# das_uhr.net
KiCad netlist of a schematic drawn in EAGLE
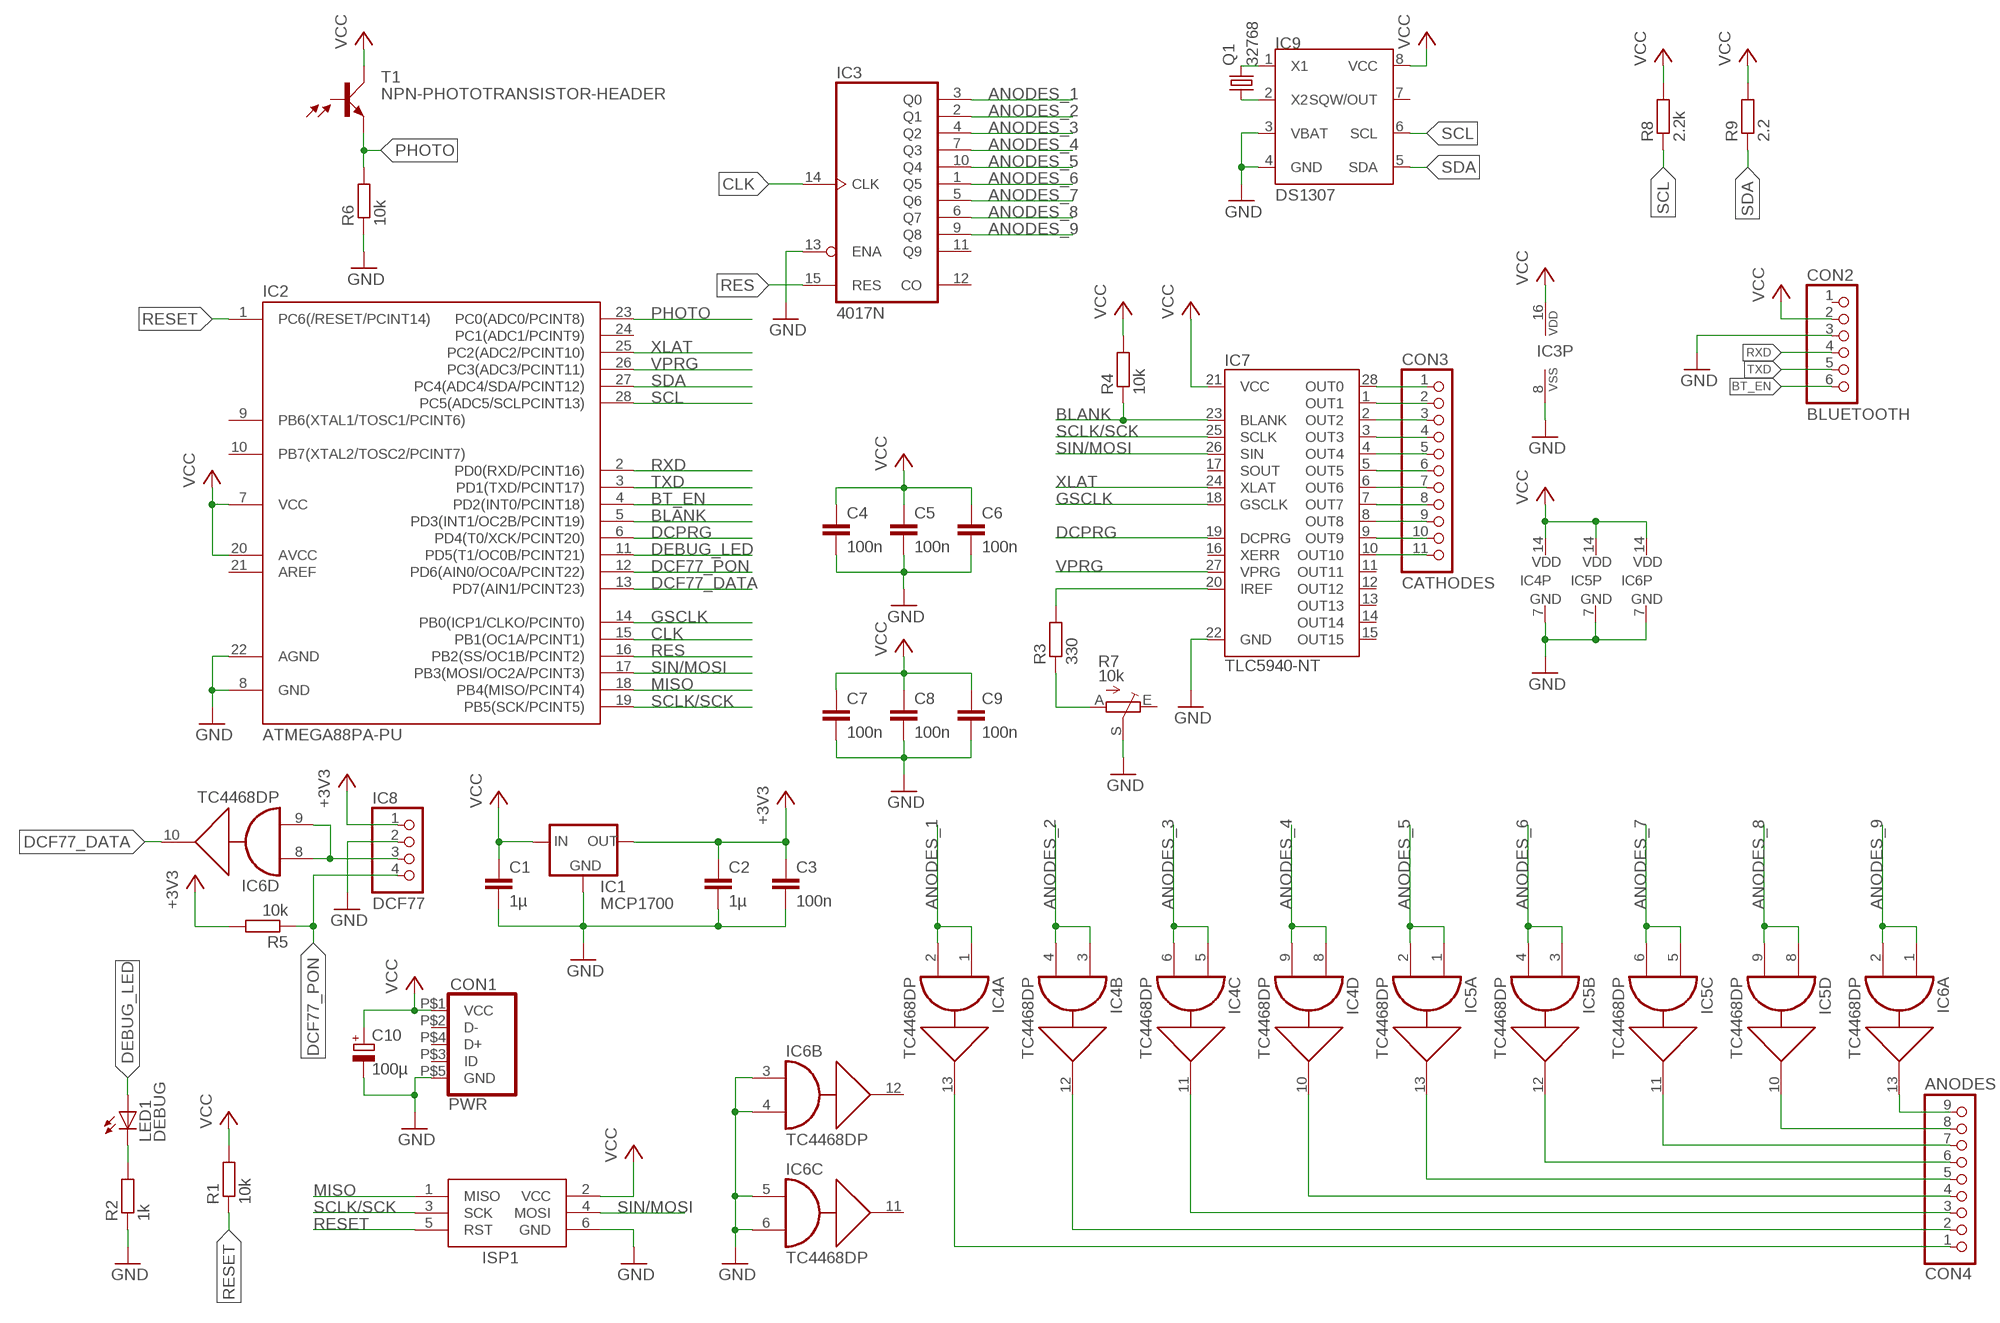
[diagram p0: schematic, sheet 1]

(export (version "E")
  (design (tool "Eeschema 10.0.6"))
  (components
    (comp (ref "C1")
      (value "1µ")
      (footprint "eagle-import:C050-024X044")
      (libsource (lib "eagle-import") (part "C050-024X044"))
    )
    (comp (ref "C2")
      (value "1µ")
      (footprint "eagle-import:C050-024X044")
      (libsource (lib "eagle-import") (part "C050-024X044"))
    )
    (comp (ref "C3")
      (value "100n")
      (footprint "eagle-import:C050-024X044")
      (libsource (lib "eagle-import") (part "C050-024X044"))
    )
    (comp (ref "C4")
      (value "100n")
      (footprint "eagle-import:C050-024X044")
      (libsource (lib "eagle-import") (part "C050-024X044"))
    )
    (comp (ref "C5")
      (value "100n")
      (footprint "eagle-import:C050-024X044")
      (libsource (lib "eagle-import") (part "C050-024X044"))
    )
    (comp (ref "C6")
      (value "100n")
      (footprint "eagle-import:C050-024X044")
      (libsource (lib "eagle-import") (part "C050-024X044"))
    )
    (comp (ref "C7")
      (value "100n")
      (footprint "eagle-import:C050-024X044")
      (libsource (lib "eagle-import") (part "C050-024X044"))
    )
    (comp (ref "C8")
      (value "100n")
      (footprint "eagle-import:C050-024X044")
      (libsource (lib "eagle-import") (part "C050-024X044"))
    )
    (comp (ref "C9")
      (value "100n")
      (footprint "eagle-import:C050-024X044")
      (libsource (lib "eagle-import") (part "C050-024X044"))
    )
    (comp (ref "C10")
      (value "100µ")
      (footprint "eagle-import:E2,5-5")
      (libsource (lib "eagle-import") (part "CPOL-EUE2.5-5"))
    )
    (comp (ref "CON1")
      (value "PWR")
      (footprint "eagle-import:HIROSE-ZX62-AB-5PA(11)")
      (libsource (lib "eagle-import") (part "USB-RECEPTABLE-HIROSE-ZX62-AB-5PA(11)"))
    )
    (comp (ref "CON2")
      (value "BLUETOOTH")
      (footprint "eagle-import:1X06")
      (libsource (lib "eagle-import") (part "PINHD-1X6"))
    )
    (comp (ref "CON3")
      (value "CATHODES")
      (footprint "eagle-import:1X11")
      (libsource (lib "eagle-import") (part "PINHD-1X11"))
    )
    (comp (ref "CON4")
      (value "ANODES")
      (footprint "eagle-import:1X09")
      (libsource (lib "eagle-import") (part "PINHD-1X9"))
    )
    (comp (ref "IC1")
      (value "MCP1700")
      (footprint "eagle-import:TO92-INLINE")
      (libsource (lib "eagle-import") (part "MCP1700INLINE"))
    )
    (comp (ref "IC2")
      (value "ATMEGA88PA-PU")
      (footprint "eagle-import:DIL28-3")
      (libsource (lib "eagle-import") (part "MEGA48/88/168-PU"))
    )
    (comp (ref "IC3")
      (value "4017N")
      (footprint "eagle-import:DIL16")
      (libsource (lib "eagle-import") (part "4017N"))
    )
    (comp (ref "IC4")
      (value "TC4468DP")
      (footprint "eagle-import:DIL14")
      (fields (field (name "MF") "MICROCHIP") (field (name "MPN") "TC4468CPD"))
      (libsource (lib "eagle-import") (part "TC4468DP"))
    )
    (comp (ref "IC5")
      (value "TC4468DP")
      (footprint "eagle-import:DIL14")
      (fields (field (name "MF") "MICROCHIP") (field (name "MPN") "TC4468CPD"))
      (libsource (lib "eagle-import") (part "TC4468DP"))
    )
    (comp (ref "IC6")
      (value "TC4468DP")
      (footprint "eagle-import:DIL14")
      (fields (field (name "MF") "MICROCHIP") (field (name "MPN") "TC4468CPD"))
      (libsource (lib "eagle-import") (part "TC4468DP"))
    )
    (comp (ref "IC7")
      (value "TLC5940-NT")
      (footprint "eagle-import:DIL28-3")
      (libsource (lib "eagle-import") (part "TLC5940-NT"))
    )
    (comp (ref "IC8")
      (value "DCF77")
      (footprint "eagle-import:1X04")
      (libsource (lib "eagle-import") (part "PINHD-1X4"))
    )
    (comp (ref "IC9")
      (value "DS1307")
      (footprint "eagle-import:DIL08")
      (libsource (lib "eagle-import") (part "DS1307"))
    )
    (comp (ref "ISP1")
      (value "AVRISP-6")
      (footprint "eagle-import:AVRISP")
      (libsource (lib "eagle-import") (part "AVRISP-6"))
    )
    (comp (ref "LED1")
      (value "DEBUG")
      (footprint "eagle-import:LED3MM")
      (libsource (lib "eagle-import") (part "LED3MM"))
    )
    (comp (ref "Q1")
      (value "32768")
      (footprint "eagle-import:TC26V")
      (libsource (lib "eagle-import") (part "CRYSTALTC26V"))
    )
    (comp (ref "R1")
      (value "10k")
      (footprint "eagle-import:0207_7")
      (libsource (lib "eagle-import") (part "R-EU_0207/7"))
    )
    (comp (ref "R2")
      (value "1k")
      (footprint "eagle-import:0207_7")
      (libsource (lib "eagle-import") (part "R-EU_0207/7"))
    )
    (comp (ref "R3")
      (value "330")
      (footprint "eagle-import:0207_7")
      (libsource (lib "eagle-import") (part "R-EU_0207/7"))
    )
    (comp (ref "R4")
      (value "10k")
      (footprint "eagle-import:0207_7")
      (libsource (lib "eagle-import") (part "R-EU_0207/7"))
    )
    (comp (ref "R5")
      (value "10k")
      (footprint "eagle-import:0207_7")
      (libsource (lib "eagle-import") (part "R-EU_0207/7"))
    )
    (comp (ref "R6")
      (value "10k")
      (footprint "eagle-import:0207_7")
      (libsource (lib "eagle-import") (part "R-EU_0207/7"))
    )
    (comp (ref "R7")
      (value "10k")
      (footprint "eagle-import:S63P")
      (libsource (lib "eagle-import") (part "TRIM_EU-S63P"))
    )
    (comp (ref "R8")
      (value "2.2k")
      (footprint "eagle-import:0207_7")
      (libsource (lib "eagle-import") (part "R-EU_0207/7"))
    )
    (comp (ref "R9")
      (value "2.2")
      (footprint "eagle-import:0207_7")
      (libsource (lib "eagle-import") (part "R-EU_0207/7"))
    )
    (comp (ref "T1")
      (value "NPN-PHOTOTRANSISTOR-HEADER")
      (footprint "eagle-import:1X02-S")
      (libsource (lib "eagle-import") (part "NPN-PHOTOTRANSISTOR-HEADER"))
    )
  )
  (nets
    (net (code "1") (name "+3V3") (class "Default")
      (node (ref "C2") (pin "1") (pinfunction "1_1") (pintype "passive"))
      (node (ref "C3") (pin "1") (pinfunction "1_1") (pintype "passive"))
      (node (ref "IC1") (pin "3") (pinfunction "OUT_3") (pintype "passive"))
      (node (ref "IC8") (pin "1") (pinfunction "1_1") (pintype "passive"))
      (node (ref "R5") (pin "2") (pinfunction "2_2") (pintype "passive"))
    )
    (net (code "2") (name "/ANODES_1") (class "Default")
      (node (ref "IC3") (pin "3") (pinfunction "Q0_3") (pintype "output"))
      (node (ref "IC4") (pin "1") (pinfunction "A_1") (pintype "input"))
      (node (ref "IC4") (pin "2") (pinfunction "B_2") (pintype "input"))
    )
    (net (code "3") (name "/ANODES_2") (class "Default")
      (node (ref "IC3") (pin "2") (pinfunction "Q1_2") (pintype "output"))
      (node (ref "IC4") (pin "3") (pinfunction "A_3") (pintype "input"))
      (node (ref "IC4") (pin "4") (pinfunction "B_4") (pintype "input"))
    )
    (net (code "4") (name "/ANODES_3") (class "Default")
      (node (ref "IC3") (pin "4") (pinfunction "Q2_4") (pintype "output"))
      (node (ref "IC4") (pin "5") (pinfunction "A_5") (pintype "input"))
      (node (ref "IC4") (pin "6") (pinfunction "B_6") (pintype "input"))
    )
    (net (code "5") (name "/ANODES_4") (class "Default")
      (node (ref "IC3") (pin "7") (pinfunction "Q3_7") (pintype "output"))
      (node (ref "IC4") (pin "8") (pinfunction "A_8") (pintype "input"))
      (node (ref "IC4") (pin "9") (pinfunction "B_9") (pintype "input"))
    )
    (net (code "6") (name "/ANODES_5") (class "Default")
      (node (ref "IC3") (pin "10") (pinfunction "Q4_10") (pintype "output"))
      (node (ref "IC5") (pin "1") (pinfunction "A_1") (pintype "input"))
      (node (ref "IC5") (pin "2") (pinfunction "B_2") (pintype "input"))
    )
    (net (code "7") (name "/ANODES_6") (class "Default")
      (node (ref "IC3") (pin "1") (pinfunction "Q5_1") (pintype "output"))
      (node (ref "IC5") (pin "3") (pinfunction "A_3") (pintype "input"))
      (node (ref "IC5") (pin "4") (pinfunction "B_4") (pintype "input"))
    )
    (net (code "8") (name "/ANODES_7") (class "Default")
      (node (ref "IC3") (pin "5") (pinfunction "Q6_5") (pintype "output"))
      (node (ref "IC5") (pin "5") (pinfunction "A_5") (pintype "input"))
      (node (ref "IC5") (pin "6") (pinfunction "B_6") (pintype "input"))
    )
    (net (code "9") (name "/ANODES_8") (class "Default")
      (node (ref "IC3") (pin "6") (pinfunction "Q7_6") (pintype "output"))
      (node (ref "IC5") (pin "8") (pinfunction "A_8") (pintype "input"))
      (node (ref "IC5") (pin "9") (pinfunction "B_9") (pintype "input"))
    )
    (net (code "10") (name "/ANODES_9") (class "Default")
      (node (ref "IC3") (pin "9") (pinfunction "Q8_9") (pintype "output"))
      (node (ref "IC6") (pin "1") (pinfunction "A_1") (pintype "input"))
      (node (ref "IC6") (pin "2") (pinfunction "B_2") (pintype "input"))
    )
    (net (code "11") (name "/BLANK") (class "Default")
      (node (ref "IC2") (pin "5") (pinfunction "PD3(INT1/OC2B/PCINT19)_5") (pintype "bidirectional"))
      (node (ref "IC7") (pin "23") (pinfunction "BLANK_23") (pintype "bidirectional"))
      (node (ref "R4") (pin "1") (pinfunction "1_1") (pintype "passive"))
    )
    (net (code "12") (name "/DCPRG") (class "Default")
      (node (ref "IC2") (pin "6") (pinfunction "PD4(T0/XCK/PCINT20)_6") (pintype "bidirectional"))
      (node (ref "IC7") (pin "19") (pinfunction "DCPRG_19") (pintype "bidirectional"))
    )
    (net (code "13") (name "/GSCLK") (class "Default")
      (node (ref "IC2") (pin "14") (pinfunction "PB0(ICP1/CLKO/PCINT0)_14") (pintype "bidirectional"))
      (node (ref "IC7") (pin "18") (pinfunction "GSCLK_18") (pintype "bidirectional"))
    )
    (net (code "14") (name "/MISO") (class "Default")
      (node (ref "IC2") (pin "18") (pinfunction "PB4(MISO/PCINT4)_18") (pintype "bidirectional"))
      (node (ref "ISP1") (pin "1") (pinfunction "MISO_1") (pintype "input"))
    )
    (net (code "15") (name "/SCLK{slash}SCK") (class "Default")
      (node (ref "IC2") (pin "19") (pinfunction "PB5(SCK/PCINT5)_19") (pintype "bidirectional"))
      (node (ref "IC7") (pin "25") (pinfunction "SCLK_25") (pintype "bidirectional"))
      (node (ref "ISP1") (pin "3") (pinfunction "SCK_3") (pintype "output"))
    )
    (net (code "16") (name "/SIN{slash}MOSI") (class "Default")
      (node (ref "IC2") (pin "17") (pinfunction "PB3(MOSI/OC2A/PCINT3)_17") (pintype "bidirectional"))
      (node (ref "IC7") (pin "26") (pinfunction "SIN_26") (pintype "bidirectional"))
      (node (ref "ISP1") (pin "4") (pinfunction "MOSI_4") (pintype "output"))
    )
    (net (code "17") (name "/VPRG") (class "Default")
      (node (ref "IC2") (pin "26") (pinfunction "PC3(ADC3/PCINT11)_26") (pintype "bidirectional"))
      (node (ref "IC7") (pin "27") (pinfunction "VPRG_27") (pintype "bidirectional"))
    )
    (net (code "18") (name "/XLAT") (class "Default")
      (node (ref "IC2") (pin "25") (pinfunction "PC2(ADC2/PCINT10)_25") (pintype "bidirectional"))
      (node (ref "IC7") (pin "24") (pinfunction "XLAT_24") (pintype "bidirectional"))
    )
    (net (code "19") (name "BT_EN") (class "Default")
      (node (ref "CON2") (pin "6") (pinfunction "6_6") (pintype "passive"))
      (node (ref "IC2") (pin "4") (pinfunction "PD2(INT0/PCINT18)_4") (pintype "bidirectional"))
    )
    (net (code "20") (name "CLK") (class "Default")
      (node (ref "IC2") (pin "15") (pinfunction "PB1(OC1A/PCINT1)_15") (pintype "bidirectional"))
      (node (ref "IC3") (pin "14") (pinfunction "CLK_14") (pintype "input"))
    )
    (net (code "21") (name "DCF77_DATA") (class "Default")
      (node (ref "IC2") (pin "13") (pinfunction "PD7(AIN1/PCINT23)_13") (pintype "bidirectional"))
      (node (ref "IC6") (pin "10") (pinfunction "Y_10") (pintype "output"))
    )
    (net (code "22") (name "DCF77_PON") (class "Default")
      (node (ref "IC2") (pin "12") (pinfunction "PD6(AIN0/OC0A/PCINT22)_12") (pintype "bidirectional"))
      (node (ref "IC8") (pin "4") (pinfunction "4_4") (pintype "passive"))
      (node (ref "R5") (pin "1") (pinfunction "1_1") (pintype "passive"))
    )
    (net (code "23") (name "DEBUG_LED") (class "Default")
      (node (ref "IC2") (pin "11") (pinfunction "PD5(T1/OC0B/PCINT21)_11") (pintype "bidirectional"))
      (node (ref "LED1") (pin "A") (pinfunction "A_A") (pintype "passive"))
    )
    (net (code "24") (name "GND") (class "Default")
      (node (ref "C1") (pin "2") (pinfunction "2_2") (pintype "passive"))
      (node (ref "C10") (pin "-") (pinfunction "-_-") (pintype "passive"))
      (node (ref "C2") (pin "2") (pinfunction "2_2") (pintype "passive"))
      (node (ref "C3") (pin "2") (pinfunction "2_2") (pintype "passive"))
      (node (ref "C4") (pin "2") (pinfunction "2_2") (pintype "passive"))
      (node (ref "C5") (pin "2") (pinfunction "2_2") (pintype "passive"))
      (node (ref "C6") (pin "2") (pinfunction "2_2") (pintype "passive"))
      (node (ref "C7") (pin "2") (pinfunction "2_2") (pintype "passive"))
      (node (ref "C8") (pin "2") (pinfunction "2_2") (pintype "passive"))
      (node (ref "C9") (pin "2") (pinfunction "2_2") (pintype "passive"))
      (node (ref "CON1") (pin "P$5") (pinfunction "GND_P$5") (pintype "bidirectional"))
      (node (ref "CON2") (pin "3") (pinfunction "3_3") (pintype "passive"))
      (node (ref "IC1") (pin "1") (pinfunction "GND_1") (pintype "input"))
      (node (ref "IC2") (pin "22") (pinfunction "AGND_22") (pintype "power_in"))
      (node (ref "IC2") (pin "8") (pinfunction "GND_8") (pintype "power_in"))
      (node (ref "IC3") (pin "13") (pinfunction "ENA_13") (pintype "input"))
      (node (ref "IC3") (pin "8") (pinfunction "VSS_8") (pintype "power_in"))
      (node (ref "IC4") (pin "7") (pinfunction "GND_7") (pintype "power_in"))
      (node (ref "IC5") (pin "7") (pinfunction "GND_7") (pintype "power_in"))
      (node (ref "IC6") (pin "3") (pinfunction "A_3") (pintype "input"))
      (node (ref "IC6") (pin "4") (pinfunction "B_4") (pintype "input"))
      (node (ref "IC6") (pin "5") (pinfunction "A_5") (pintype "input"))
      (node (ref "IC6") (pin "6") (pinfunction "B_6") (pintype "input"))
      (node (ref "IC6") (pin "7") (pinfunction "GND_7") (pintype "power_in"))
      (node (ref "IC7") (pin "22") (pinfunction "GND_22") (pintype "bidirectional"))
      (node (ref "IC8") (pin "2") (pinfunction "2_2") (pintype "passive"))
      (node (ref "IC9") (pin "3") (pinfunction "VBAT_3") (pintype "power_in"))
      (node (ref "IC9") (pin "4") (pinfunction "GND_4") (pintype "power_in"))
      (node (ref "ISP1") (pin "6") (pinfunction "GND_6") (pintype "power_in"))
      (node (ref "R2") (pin "1") (pinfunction "1_1") (pintype "passive"))
      (node (ref "R6") (pin "1") (pinfunction "1_1") (pintype "passive"))
      (node (ref "R7") (pin "S") (pinfunction "S_S") (pintype "passive"))
    )
    (net (code "25") (name "Net-(IC4A-Y)") (class "Default")
      (node (ref "CON4") (pin "1") (pinfunction "1_1") (pintype "passive"))
      (node (ref "IC4") (pin "13") (pinfunction "Y_13") (pintype "output"))
    )
    (net (code "26") (name "Net-(IC4B-Y)") (class "Default")
      (node (ref "CON4") (pin "2") (pinfunction "2_2") (pintype "passive"))
      (node (ref "IC4") (pin "12") (pinfunction "Y_12") (pintype "output"))
    )
    (net (code "27") (name "Net-(IC4C-Y)") (class "Default")
      (node (ref "CON4") (pin "3") (pinfunction "3_3") (pintype "passive"))
      (node (ref "IC4") (pin "11") (pinfunction "Y_11") (pintype "output"))
    )
    (net (code "28") (name "Net-(IC4D-Y)") (class "Default")
      (node (ref "CON4") (pin "4") (pinfunction "4_4") (pintype "passive"))
      (node (ref "IC4") (pin "10") (pinfunction "Y_10") (pintype "output"))
    )
    (net (code "29") (name "Net-(IC5A-Y)") (class "Default")
      (node (ref "CON4") (pin "5") (pinfunction "5_5") (pintype "passive"))
      (node (ref "IC5") (pin "13") (pinfunction "Y_13") (pintype "output"))
    )
    (net (code "30") (name "Net-(IC5B-Y)") (class "Default")
      (node (ref "CON4") (pin "6") (pinfunction "6_6") (pintype "passive"))
      (node (ref "IC5") (pin "12") (pinfunction "Y_12") (pintype "output"))
    )
    (net (code "31") (name "Net-(IC5C-Y)") (class "Default")
      (node (ref "CON4") (pin "7") (pinfunction "7_7") (pintype "passive"))
      (node (ref "IC5") (pin "11") (pinfunction "Y_11") (pintype "output"))
    )
    (net (code "32") (name "Net-(IC5D-Y)") (class "Default")
      (node (ref "CON4") (pin "8") (pinfunction "8_8") (pintype "passive"))
      (node (ref "IC5") (pin "10") (pinfunction "Y_10") (pintype "output"))
    )
    (net (code "33") (name "Net-(IC6A-Y)") (class "Default")
      (node (ref "CON4") (pin "9") (pinfunction "9_9") (pintype "passive"))
      (node (ref "IC6") (pin "13") (pinfunction "Y_13") (pintype "output"))
    )
    (net (code "34") (name "Net-(IC6D-A)") (class "Default")
      (node (ref "IC6") (pin "8") (pinfunction "A_8") (pintype "input"))
      (node (ref "IC6") (pin "9") (pinfunction "B_9") (pintype "input"))
      (node (ref "IC8") (pin "3") (pinfunction "3_3") (pintype "passive"))
    )
    (net (code "35") (name "Net-(IC7-IREF)") (class "Default")
      (node (ref "IC7") (pin "20") (pinfunction "IREF_20") (pintype "bidirectional"))
      (node (ref "R3") (pin "2") (pinfunction "2_2") (pintype "passive"))
    )
    (net (code "36") (name "Net-(IC7-OUT0)") (class "Default")
      (node (ref "CON3") (pin "1") (pinfunction "1_1") (pintype "passive"))
      (node (ref "IC7") (pin "28") (pinfunction "OUT0_28") (pintype "bidirectional"))
    )
    (net (code "37") (name "Net-(IC7-OUT1)") (class "Default")
      (node (ref "CON3") (pin "2") (pinfunction "2_2") (pintype "passive"))
      (node (ref "IC7") (pin "1") (pinfunction "OUT1_1") (pintype "bidirectional"))
    )
    (net (code "38") (name "Net-(IC7-OUT2)") (class "Default")
      (node (ref "CON3") (pin "3") (pinfunction "3_3") (pintype "passive"))
      (node (ref "IC7") (pin "2") (pinfunction "OUT2_2") (pintype "bidirectional"))
    )
    (net (code "39") (name "Net-(IC7-OUT3)") (class "Default")
      (node (ref "CON3") (pin "4") (pinfunction "4_4") (pintype "passive"))
      (node (ref "IC7") (pin "3") (pinfunction "OUT3_3") (pintype "bidirectional"))
    )
    (net (code "40") (name "Net-(IC7-OUT4)") (class "Default")
      (node (ref "CON3") (pin "5") (pinfunction "5_5") (pintype "passive"))
      (node (ref "IC7") (pin "4") (pinfunction "OUT4_4") (pintype "bidirectional"))
    )
    (net (code "41") (name "Net-(IC7-OUT5)") (class "Default")
      (node (ref "CON3") (pin "6") (pinfunction "6_6") (pintype "passive"))
      (node (ref "IC7") (pin "5") (pinfunction "OUT5_5") (pintype "bidirectional"))
    )
    (net (code "42") (name "Net-(IC7-OUT6)") (class "Default")
      (node (ref "CON3") (pin "7") (pinfunction "7_7") (pintype "passive"))
      (node (ref "IC7") (pin "6") (pinfunction "OUT6_6") (pintype "bidirectional"))
    )
    (net (code "43") (name "Net-(IC7-OUT7)") (class "Default")
      (node (ref "CON3") (pin "8") (pinfunction "8_8") (pintype "passive"))
      (node (ref "IC7") (pin "7") (pinfunction "OUT7_7") (pintype "bidirectional"))
    )
    (net (code "44") (name "Net-(IC7-OUT8)") (class "Default")
      (node (ref "CON3") (pin "9") (pinfunction "9_9") (pintype "passive"))
      (node (ref "IC7") (pin "8") (pinfunction "OUT8_8") (pintype "bidirectional"))
    )
    (net (code "45") (name "Net-(IC7-OUT9)") (class "Default")
      (node (ref "CON3") (pin "10") (pinfunction "10_10") (pintype "passive"))
      (node (ref "IC7") (pin "9") (pinfunction "OUT9_9") (pintype "bidirectional"))
    )
    (net (code "46") (name "Net-(IC7-OUT10)") (class "Default")
      (node (ref "CON3") (pin "11") (pinfunction "11_11") (pintype "passive"))
      (node (ref "IC7") (pin "10") (pinfunction "OUT10_10") (pintype "bidirectional"))
    )
    (net (code "47") (name "Net-(IC9-X1)") (class "Default")
      (node (ref "IC9") (pin "1") (pinfunction "X1_1") (pintype "input"))
      (node (ref "Q1") (pin "2") (pinfunction "2_2") (pintype "passive"))
    )
    (net (code "48") (name "Net-(IC9-X2)") (class "Default")
      (node (ref "IC9") (pin "2") (pinfunction "X2_2") (pintype "output"))
      (node (ref "Q1") (pin "1") (pinfunction "1_1") (pintype "passive"))
    )
    (net (code "49") (name "Net-(LED1-C)") (class "Default")
      (node (ref "LED1") (pin "K") (pinfunction "C_K") (pintype "passive"))
      (node (ref "R2") (pin "2") (pinfunction "2_2") (pintype "passive"))
    )
    (net (code "50") (name "Net-(R3-Pad1)") (class "Default")
      (node (ref "R3") (pin "1") (pinfunction "1_1") (pintype "passive"))
      (node (ref "R7") (pin "A") (pinfunction "A_A") (pintype "passive"))
    )
    (net (code "51") (name "PHOTO") (class "Default")
      (node (ref "IC2") (pin "23") (pinfunction "PC0(ADC0/PCINT8)_23") (pintype "bidirectional"))
      (node (ref "R6") (pin "2") (pinfunction "2_2") (pintype "passive"))
      (node (ref "T1") (pin "2") (pinfunction "E_2") (pintype "passive"))
    )
    (net (code "52") (name "RES") (class "Default")
      (node (ref "IC2") (pin "16") (pinfunction "PB2(SS/OC1B/PCINT2)_16") (pintype "bidirectional"))
      (node (ref "IC3") (pin "15") (pinfunction "RES_15") (pintype "input"))
    )
    (net (code "53") (name "RESET") (class "Default")
      (node (ref "IC2") (pin "1") (pinfunction "PC6(/RESET/PCINT14)_1") (pintype "bidirectional"))
      (node (ref "ISP1") (pin "5") (pinfunction "RST_5") (pintype "output"))
      (node (ref "R1") (pin "1") (pinfunction "1_1") (pintype "passive"))
    )
    (net (code "54") (name "RXD") (class "Default")
      (node (ref "CON2") (pin "4") (pinfunction "4_4") (pintype "passive"))
      (node (ref "IC2") (pin "2") (pinfunction "PD0(RXD/PCINT16)_2") (pintype "bidirectional"))
    )
    (net (code "55") (name "SCL") (class "Default")
      (node (ref "IC2") (pin "28") (pinfunction "PC5(ADC5/SCLPCINT13)_28") (pintype "bidirectional"))
      (node (ref "IC9") (pin "6") (pinfunction "SCL_6") (pintype "input"))
      (node (ref "R8") (pin "1") (pinfunction "1_1") (pintype "passive"))
    )
    (net (code "56") (name "SDA") (class "Default")
      (node (ref "IC2") (pin "27") (pinfunction "PC4(ADC4/SDA/PCINT12)_27") (pintype "bidirectional"))
      (node (ref "IC9") (pin "5") (pinfunction "SDA_5") (pintype "bidirectional"))
      (node (ref "R9") (pin "1") (pinfunction "1_1") (pintype "passive"))
    )
    (net (code "57") (name "TXD") (class "Default")
      (node (ref "CON2") (pin "5") (pinfunction "5_5") (pintype "passive"))
      (node (ref "IC2") (pin "3") (pinfunction "PD1(TXD/PCINT17)_3") (pintype "bidirectional"))
    )
    (net (code "58") (name "VCC") (class "Default")
      (node (ref "C1") (pin "1") (pinfunction "1_1") (pintype "passive"))
      (node (ref "C10") (pin "+") (pinfunction "+_+") (pintype "passive"))
      (node (ref "C4") (pin "1") (pinfunction "1_1") (pintype "passive"))
      (node (ref "C5") (pin "1") (pinfunction "1_1") (pintype "passive"))
      (node (ref "C6") (pin "1") (pinfunction "1_1") (pintype "passive"))
      (node (ref "C7") (pin "1") (pinfunction "1_1") (pintype "passive"))
      (node (ref "C8") (pin "1") (pinfunction "1_1") (pintype "passive"))
      (node (ref "C9") (pin "1") (pinfunction "1_1") (pintype "passive"))
      (node (ref "CON1") (pin "P$1") (pinfunction "VCC_P$1") (pintype "bidirectional"))
      (node (ref "CON2") (pin "2") (pinfunction "2_2") (pintype "passive"))
      (node (ref "IC1") (pin "2") (pinfunction "IN_2") (pintype "input"))
      (node (ref "IC2") (pin "20") (pinfunction "AVCC_20") (pintype "passive"))
      (node (ref "IC2") (pin "7") (pinfunction "VCC_7") (pintype "power_in"))
      (node (ref "IC3") (pin "16") (pinfunction "VDD_16") (pintype "power_in"))
      (node (ref "IC4") (pin "14") (pinfunction "VDD_14") (pintype "power_in"))
      (node (ref "IC5") (pin "14") (pinfunction "VDD_14") (pintype "power_in"))
      (node (ref "IC6") (pin "14") (pinfunction "VDD_14") (pintype "power_in"))
      (node (ref "IC7") (pin "21") (pinfunction "VCC_21") (pintype "bidirectional"))
      (node (ref "IC9") (pin "8") (pinfunction "VCC_8") (pintype "power_in"))
      (node (ref "ISP1") (pin "2") (pinfunction "VCC_2") (pintype "power_in"))
      (node (ref "R1") (pin "2") (pinfunction "2_2") (pintype "passive"))
      (node (ref "R4") (pin "2") (pinfunction "2_2") (pintype "passive"))
      (node (ref "R8") (pin "2") (pinfunction "2_2") (pintype "passive"))
      (node (ref "R9") (pin "2") (pinfunction "2_2") (pintype "passive"))
      (node (ref "T1") (pin "1") (pinfunction "C_1") (pintype "passive"))
    )
    (net (code "59") (name "unconnected-(CON1-D+-PadP$4)") (class "Default")
      (node (ref "CON1") (pin "P$4") (pinfunction "D+_P$4") (pintype "bidirectional"))
    )
    (net (code "60") (name "unconnected-(CON1-D--PadP$2)") (class "Default")
      (node (ref "CON1") (pin "P$2") (pinfunction "D-_P$2") (pintype "bidirectional"))
    )
    (net (code "61") (name "unconnected-(CON1-ID-PadP$3)") (class "Default")
      (node (ref "CON1") (pin "P$3") (pinfunction "ID_P$3") (pintype "bidirectional"))
    )
    (net (code "62") (name "unconnected-(CON2-Pad1)") (class "Default")
      (node (ref "CON2") (pin "1") (pinfunction "1_1") (pintype "passive"))
    )
    (net (code "63") (name "unconnected-(IC2-AREF-Pad21)") (class "Default")
      (node (ref "IC2") (pin "21") (pinfunction "AREF_21") (pintype "passive"))
    )
    (net (code "64") (name "unconnected-(IC2-PB6(XTAL1{slash}TOSC1{slash}PCINT6)-Pad9)") (class "Default")
      (node (ref "IC2") (pin "9") (pinfunction "PB6(XTAL1/TOSC1/PCINT6)_9") (pintype "bidirectional"))
    )
    (net (code "65") (name "unconnected-(IC2-PB7(XTAL2{slash}TOSC2{slash}PCINT7)-Pad10)") (class "Default")
      (node (ref "IC2") (pin "10") (pinfunction "PB7(XTAL2/TOSC2/PCINT7)_10") (pintype "bidirectional"))
    )
    (net (code "66") (name "unconnected-(IC2-PC1(ADC1{slash}PCINT9)-Pad24)") (class "Default")
      (node (ref "IC2") (pin "24") (pinfunction "PC1(ADC1/PCINT9)_24") (pintype "bidirectional"))
    )
    (net (code "67") (name "unconnected-(IC3A-CO-Pad12)") (class "Default")
      (node (ref "IC3") (pin "12") (pinfunction "CO_12") (pintype "output"))
    )
    (net (code "68") (name "unconnected-(IC3A-Q9-Pad11)") (class "Default")
      (node (ref "IC3") (pin "11") (pinfunction "Q9_11") (pintype "output"))
    )
    (net (code "69") (name "unconnected-(IC6B-Y-Pad12)") (class "Default")
      (node (ref "IC6") (pin "12") (pinfunction "Y_12") (pintype "output"))
    )
    (net (code "70") (name "unconnected-(IC6C-Y-Pad11)") (class "Default")
      (node (ref "IC6") (pin "11") (pinfunction "Y_11") (pintype "output"))
    )
    (net (code "71") (name "unconnected-(IC7-OUT11-Pad11)") (class "Default")
      (node (ref "IC7") (pin "11") (pinfunction "OUT11_11") (pintype "bidirectional"))
    )
    (net (code "72") (name "unconnected-(IC7-OUT12-Pad12)") (class "Default")
      (node (ref "IC7") (pin "12") (pinfunction "OUT12_12") (pintype "bidirectional"))
    )
    (net (code "73") (name "unconnected-(IC7-OUT13-Pad13)") (class "Default")
      (node (ref "IC7") (pin "13") (pinfunction "OUT13_13") (pintype "bidirectional"))
    )
    (net (code "74") (name "unconnected-(IC7-OUT14-Pad14)") (class "Default")
      (node (ref "IC7") (pin "14") (pinfunction "OUT14_14") (pintype "bidirectional"))
    )
    (net (code "75") (name "unconnected-(IC7-OUT15-Pad15)") (class "Default")
      (node (ref "IC7") (pin "15") (pinfunction "OUT15_15") (pintype "bidirectional"))
    )
    (net (code "76") (name "unconnected-(IC7-SOUT-Pad17)") (class "Default")
      (node (ref "IC7") (pin "17") (pinfunction "SOUT_17") (pintype "bidirectional"))
    )
    (net (code "77") (name "unconnected-(IC7-XERR-Pad16)") (class "Default")
      (node (ref "IC7") (pin "16") (pinfunction "XERR_16") (pintype "bidirectional"))
    )
    (net (code "78") (name "unconnected-(IC9-SQW{slash}OUT-Pad7)") (class "Default")
      (node (ref "IC9") (pin "7") (pinfunction "SQW/OUT_7") (pintype "output"))
    )
    (net (code "79") (name "unconnected-(R7-PadE)") (class "Default")
      (node (ref "R7") (pin "E") (pinfunction "E_E") (pintype "passive"))
    )
  )
)
